# untitled.net
KiCad netlist of a schematic drawn in EAGLE
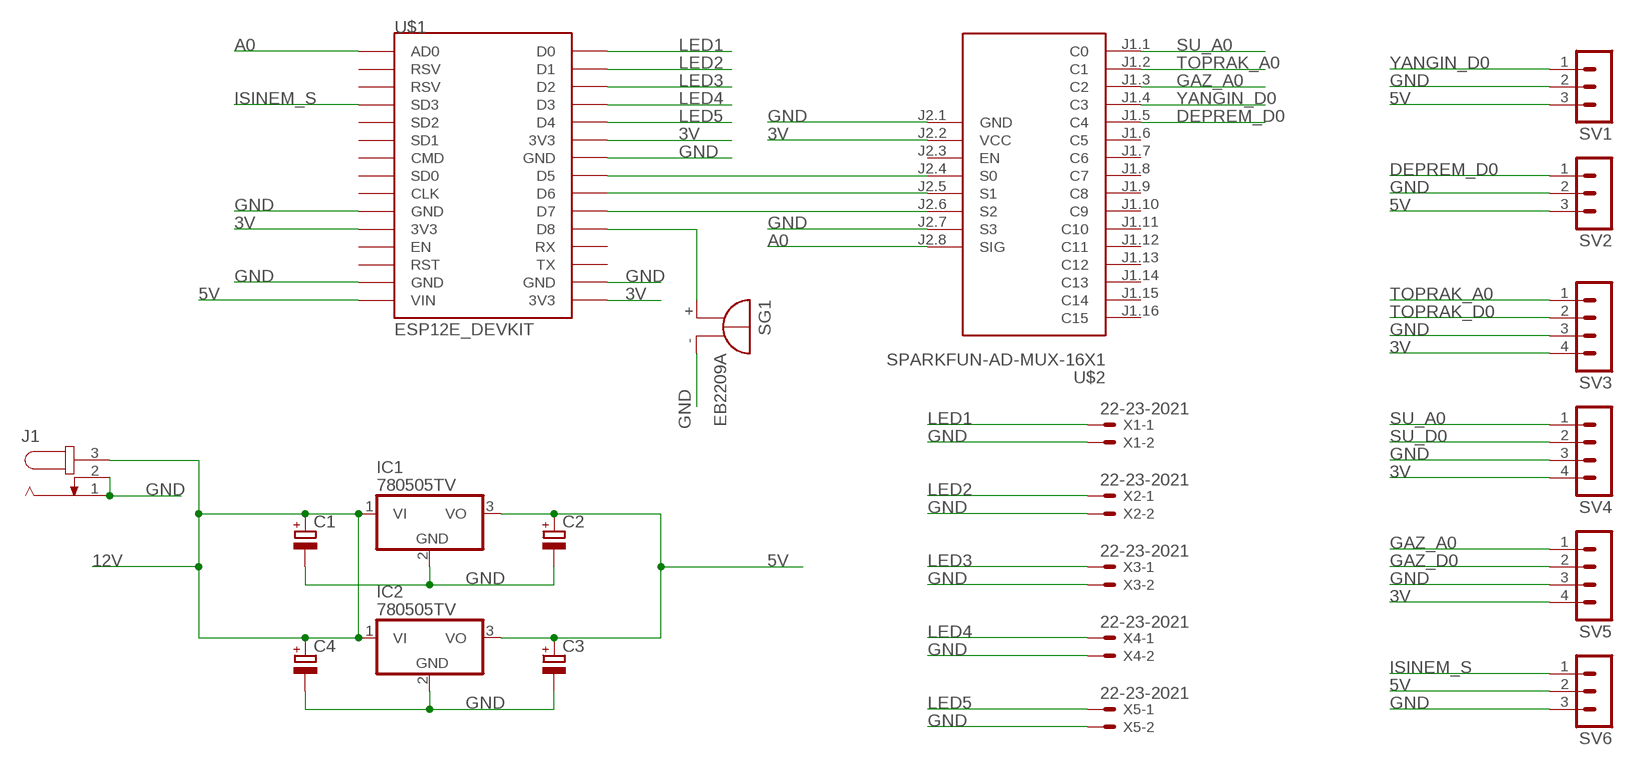
[diagram p0: schematic, sheet 1]

(export (version "E")
  (design (tool "Eeschema 10.0.6"))
  (components
    (comp (ref "C1")
      (value "CPOL-EUE5-5")
      (footprint "eagle-import:E5-5")
      (libsource (lib "eagle-import") (part "CPOL-EUE5-5"))
    )
    (comp (ref "C2")
      (value "CPOL-EUE5-5")
      (footprint "eagle-import:E5-5")
      (libsource (lib "eagle-import") (part "CPOL-EUE5-5"))
    )
    (comp (ref "C3")
      (value "CPOL-EUE5-5")
      (footprint "eagle-import:E5-5")
      (libsource (lib "eagle-import") (part "CPOL-EUE5-5"))
    )
    (comp (ref "C4")
      (value "CPOL-EUE5-5")
      (footprint "eagle-import:E5-5")
      (libsource (lib "eagle-import") (part "CPOL-EUE5-5"))
    )
    (comp (ref "IC1")
      (value "780505TV")
      (footprint "eagle-import:TO220V")
      (libsource (lib "eagle-import") (part "7805TV05"))
    )
    (comp (ref "IC2")
      (value "780505TV")
      (footprint "eagle-import:TO220V")
      (libsource (lib "eagle-import") (part "7805TV05"))
    )
    (comp (ref "J1")
      (value "JACK-PLUG1")
      (footprint "eagle-import:SPC4078")
      (libsource (lib "eagle-import") (part "JACK-PLUG1"))
    )
    (comp (ref "SG1")
      (value "EB2209A")
      (footprint "eagle-import:EB2209A")
      (libsource (lib "eagle-import") (part "EB2209A"))
    )
    (comp (ref "SV1")
      (value "MA03-1")
      (footprint "eagle-import:MA03-1")
      (libsource (lib "eagle-import") (part "MA03-1"))
    )
    (comp (ref "SV2")
      (value "MA03-1")
      (footprint "eagle-import:MA03-1")
      (libsource (lib "eagle-import") (part "MA03-1"))
    )
    (comp (ref "SV3")
      (value "MA04-1")
      (footprint "eagle-import:MA04-1")
      (libsource (lib "eagle-import") (part "MA04-1"))
    )
    (comp (ref "SV4")
      (value "MA04-1")
      (footprint "eagle-import:MA04-1")
      (libsource (lib "eagle-import") (part "MA04-1"))
    )
    (comp (ref "SV5")
      (value "MA04-1")
      (footprint "eagle-import:MA04-1")
      (libsource (lib "eagle-import") (part "MA04-1"))
    )
    (comp (ref "SV6")
      (value "MA03-1")
      (footprint "eagle-import:MA03-1")
      (libsource (lib "eagle-import") (part "MA03-1"))
    )
    (comp (ref "U$1")
      (value "ESP12E_DEVKIT")
      (footprint "eagle-import:ESP12E_DEVKIT")
      (libsource (lib "eagle-import") (part "ESP12E_DEVKIT"))
    )
    (comp (ref "U$2")
      (value "SPARKFUN-AD-MUX-16X1")
      (footprint "eagle-import:SPARKFUN-AD-MUX-16X1")
      (libsource (lib "eagle-import") (part "SPARKFUN-AD-MUX-16X1"))
    )
    (comp (ref "X1")
      (value "22-23-2021")
      (footprint "eagle-import:22-23-2021")
      (fields (field (name "MF") "MOLEX"))
      (libsource (lib "eagle-import") (part "22-23-2021"))
    )
    (comp (ref "X2")
      (value "22-23-2021")
      (footprint "eagle-import:22-23-2021")
      (fields (field (name "MF") "MOLEX"))
      (libsource (lib "eagle-import") (part "22-23-2021"))
    )
    (comp (ref "X3")
      (value "22-23-2021")
      (footprint "eagle-import:22-23-2021")
      (fields (field (name "MF") "MOLEX"))
      (libsource (lib "eagle-import") (part "22-23-2021"))
    )
    (comp (ref "X4")
      (value "22-23-2021")
      (footprint "eagle-import:22-23-2021")
      (fields (field (name "MF") "MOLEX"))
      (libsource (lib "eagle-import") (part "22-23-2021"))
    )
    (comp (ref "X5")
      (value "22-23-2021")
      (footprint "eagle-import:22-23-2021")
      (fields (field (name "MF") "MOLEX"))
      (libsource (lib "eagle-import") (part "22-23-2021"))
    )
  )
  (nets
    (net (code "1") (name "/3V") (class "Default")
      (node (ref "SV3") (pin "4") (pinfunction "4_4") (pintype "passive"))
      (node (ref "SV4") (pin "4") (pinfunction "4_4") (pintype "passive"))
      (node (ref "SV5") (pin "4") (pinfunction "4_4") (pintype "passive"))
      (node (ref "U$1") (pin "3V3@0") (pinfunction "3V3_3V3@0") (pintype "bidirectional"))
      (node (ref "U$1") (pin "3V3@1") (pinfunction "3V3_3V3@1") (pintype "bidirectional"))
      (node (ref "U$1") (pin "3V3@2") (pinfunction "3V3_3V3@2") (pintype "bidirectional"))
      (node (ref "U$2") (pin "J2.2") (pinfunction "VCC_J2.2") (pintype "power_in"))
    )
    (net (code "2") (name "/5V") (class "Default")
      (node (ref "C2") (pin "+") (pinfunction "+_+") (pintype "passive"))
      (node (ref "C3") (pin "+") (pinfunction "+_+") (pintype "passive"))
      (node (ref "IC1") (pin "3") (pinfunction "VO_3") (pintype "passive"))
      (node (ref "IC2") (pin "3") (pinfunction "VO_3") (pintype "passive"))
      (node (ref "SV1") (pin "3") (pinfunction "3_3") (pintype "passive"))
      (node (ref "SV2") (pin "3") (pinfunction "3_3") (pintype "passive"))
      (node (ref "SV6") (pin "2") (pinfunction "2_2") (pintype "passive"))
      (node (ref "U$1") (pin "VIN") (pinfunction "VIN_VIN") (pintype "bidirectional"))
    )
    (net (code "3") (name "/12V") (class "Default")
      (node (ref "C1") (pin "+") (pinfunction "+_+") (pintype "passive"))
      (node (ref "C4") (pin "+") (pinfunction "+_+") (pintype "passive"))
      (node (ref "IC1") (pin "1") (pinfunction "VI_1") (pintype "input"))
      (node (ref "IC2") (pin "1") (pinfunction "VI_1") (pintype "input"))
      (node (ref "J1") (pin "3") (pinfunction "3_3") (pintype "passive"))
    )
    (net (code "4") (name "/A0") (class "Default")
      (node (ref "U$1") (pin "AD0") (pinfunction "AD0_AD0") (pintype "bidirectional"))
      (node (ref "U$2") (pin "J2.8") (pinfunction "SIG_J2.8") (pintype "bidirectional"))
    )
    (net (code "5") (name "/DEPREM_D0") (class "Default")
      (node (ref "SV2") (pin "1") (pinfunction "1_1") (pintype "passive"))
      (node (ref "U$2") (pin "J1.5") (pinfunction "C4_J1.5") (pintype "bidirectional"))
    )
    (net (code "6") (name "/GAZ_A0") (class "Default")
      (node (ref "SV5") (pin "1") (pinfunction "1_1") (pintype "passive"))
      (node (ref "U$2") (pin "J1.3") (pinfunction "C2_J1.3") (pintype "bidirectional"))
    )
    (net (code "7") (name "/GAZ_D0") (class "Default")
      (node (ref "SV5") (pin "2") (pinfunction "2_2") (pintype "passive"))
    )
    (net (code "8") (name "/GND") (class "Default")
      (node (ref "C1") (pin "-") (pinfunction "-_-") (pintype "passive"))
      (node (ref "C2") (pin "-") (pinfunction "-_-") (pintype "passive"))
      (node (ref "C3") (pin "-") (pinfunction "-_-") (pintype "passive"))
      (node (ref "C4") (pin "-") (pinfunction "-_-") (pintype "passive"))
      (node (ref "IC1") (pin "2") (pinfunction "GND_2") (pintype "passive"))
      (node (ref "IC2") (pin "2") (pinfunction "GND_2") (pintype "passive"))
      (node (ref "J1") (pin "1") (pinfunction "1_1") (pintype "passive"))
      (node (ref "J1") (pin "2") (pinfunction "2_2") (pintype "passive"))
      (node (ref "SG1") (pin "-") (pinfunction "-_-") (pintype "passive"))
      (node (ref "SV1") (pin "2") (pinfunction "2_2") (pintype "passive"))
      (node (ref "SV2") (pin "2") (pinfunction "2_2") (pintype "passive"))
      (node (ref "SV3") (pin "3") (pinfunction "3_3") (pintype "passive"))
      (node (ref "SV4") (pin "3") (pinfunction "3_3") (pintype "passive"))
      (node (ref "SV5") (pin "3") (pinfunction "3_3") (pintype "passive"))
      (node (ref "SV6") (pin "3") (pinfunction "3_3") (pintype "passive"))
      (node (ref "U$1") (pin "GND@0") (pinfunction "GND_GND@0") (pintype "bidirectional"))
      (node (ref "U$1") (pin "GND@1") (pinfunction "GND_GND@1") (pintype "bidirectional"))
      (node (ref "U$1") (pin "GND@2") (pinfunction "GND_GND@2") (pintype "bidirectional"))
      (node (ref "U$1") (pin "GND@3") (pinfunction "GND_GND@3") (pintype "bidirectional"))
      (node (ref "U$2") (pin "J2.1") (pinfunction "GND_J2.1") (pintype "power_in"))
      (node (ref "U$2") (pin "J2.7") (pinfunction "S3_J2.7") (pintype "bidirectional"))
      (node (ref "X1") (pin "2") (pinfunction "S_2") (pintype "passive"))
      (node (ref "X2") (pin "2") (pinfunction "S_2") (pintype "passive"))
      (node (ref "X3") (pin "2") (pinfunction "S_2") (pintype "passive"))
      (node (ref "X4") (pin "2") (pinfunction "S_2") (pintype "passive"))
      (node (ref "X5") (pin "2") (pinfunction "S_2") (pintype "passive"))
    )
    (net (code "9") (name "/ISINEM_S") (class "Default")
      (node (ref "SV6") (pin "1") (pinfunction "1_1") (pintype "passive"))
      (node (ref "U$1") (pin "SD3") (pinfunction "SD3_SD3") (pintype "bidirectional"))
    )
    (net (code "10") (name "/LED1") (class "Default")
      (node (ref "U$1") (pin "D0") (pinfunction "D0_D0") (pintype "bidirectional"))
      (node (ref "X1") (pin "1") (pinfunction "S_1") (pintype "passive"))
    )
    (net (code "11") (name "/LED2") (class "Default")
      (node (ref "U$1") (pin "D1") (pinfunction "D1_D1") (pintype "bidirectional"))
      (node (ref "X2") (pin "1") (pinfunction "S_1") (pintype "passive"))
    )
    (net (code "12") (name "/LED3") (class "Default")
      (node (ref "U$1") (pin "D2") (pinfunction "D2_D2") (pintype "bidirectional"))
      (node (ref "X3") (pin "1") (pinfunction "S_1") (pintype "passive"))
    )
    (net (code "13") (name "/LED4") (class "Default")
      (node (ref "U$1") (pin "D3") (pinfunction "D3_D3") (pintype "bidirectional"))
      (node (ref "X4") (pin "1") (pinfunction "S_1") (pintype "passive"))
    )
    (net (code "14") (name "/LED5") (class "Default")
      (node (ref "U$1") (pin "D4") (pinfunction "D4_D4") (pintype "bidirectional"))
      (node (ref "X5") (pin "1") (pinfunction "S_1") (pintype "passive"))
    )
    (net (code "15") (name "/SU_A0") (class "Default")
      (node (ref "SV4") (pin "1") (pinfunction "1_1") (pintype "passive"))
      (node (ref "U$2") (pin "J1.1") (pinfunction "C0_J1.1") (pintype "bidirectional"))
    )
    (net (code "16") (name "/SU_D0") (class "Default")
      (node (ref "SV4") (pin "2") (pinfunction "2_2") (pintype "passive"))
    )
    (net (code "17") (name "/TOPRAK_A0") (class "Default")
      (node (ref "SV3") (pin "1") (pinfunction "1_1") (pintype "passive"))
      (node (ref "U$2") (pin "J1.2") (pinfunction "C1_J1.2") (pintype "bidirectional"))
    )
    (net (code "18") (name "/TOPRAK_D0") (class "Default")
      (node (ref "SV3") (pin "2") (pinfunction "2_2") (pintype "passive"))
    )
    (net (code "19") (name "/YANGIN_D0") (class "Default")
      (node (ref "SV1") (pin "1") (pinfunction "1_1") (pintype "passive"))
      (node (ref "U$2") (pin "J1.4") (pinfunction "C3_J1.4") (pintype "bidirectional"))
    )
    (net (code "20") (name "Net-(SG1-Pad+)") (class "Default")
      (node (ref "SG1") (pin "+") (pinfunction "+_+") (pintype "passive"))
      (node (ref "U$1") (pin "D8") (pinfunction "D8_D8") (pintype "bidirectional"))
    )
    (net (code "21") (name "Net-(U$2-S0)") (class "Default")
      (node (ref "U$1") (pin "D5") (pinfunction "D5_D5") (pintype "bidirectional"))
      (node (ref "U$2") (pin "J2.4") (pinfunction "S0_J2.4") (pintype "bidirectional"))
    )
    (net (code "22") (name "Net-(U$2-S1)") (class "Default")
      (node (ref "U$1") (pin "D6") (pinfunction "D6_D6") (pintype "bidirectional"))
      (node (ref "U$2") (pin "J2.5") (pinfunction "S1_J2.5") (pintype "bidirectional"))
    )
    (net (code "23") (name "Net-(U$2-S2)") (class "Default")
      (node (ref "U$1") (pin "D7") (pinfunction "D7_D7") (pintype "bidirectional"))
      (node (ref "U$2") (pin "J2.6") (pinfunction "S2_J2.6") (pintype "bidirectional"))
    )
    (net (code "24") (name "unconnected-(U$1-PadCLK)") (class "Default")
      (node (ref "U$1") (pin "CLK") (pinfunction "CLK_CLK") (pintype "bidirectional"))
    )
    (net (code "25") (name "unconnected-(U$1-PadCMD)") (class "Default")
      (node (ref "U$1") (pin "CMD") (pinfunction "CMD_CMD") (pintype "bidirectional"))
    )
    (net (code "26") (name "unconnected-(U$1-PadEN)") (class "Default")
      (node (ref "U$1") (pin "EN") (pinfunction "EN_EN") (pintype "bidirectional"))
    )
    (net (code "27") (name "unconnected-(U$1-PadRST)") (class "Default")
      (node (ref "U$1") (pin "RST") (pinfunction "RST_RST") (pintype "bidirectional"))
    )
    (net (code "28") (name "unconnected-(U$1-PadRX)") (class "Default")
      (node (ref "U$1") (pin "RX") (pinfunction "RX_RX") (pintype "bidirectional"))
    )
    (net (code "29") (name "unconnected-(U$1-PadSD0)") (class "Default")
      (node (ref "U$1") (pin "SD0") (pinfunction "SD0_SD0") (pintype "bidirectional"))
    )
    (net (code "30") (name "unconnected-(U$1-PadSD1)") (class "Default")
      (node (ref "U$1") (pin "SD1") (pinfunction "SD1_SD1") (pintype "bidirectional"))
    )
    (net (code "31") (name "unconnected-(U$1-PadSD2)") (class "Default")
      (node (ref "U$1") (pin "SD2") (pinfunction "SD2_SD2") (pintype "bidirectional"))
    )
    (net (code "32") (name "unconnected-(U$1-PadTX)") (class "Default")
      (node (ref "U$1") (pin "TX") (pinfunction "TX_TX") (pintype "bidirectional"))
    )
    (net (code "33") (name "unconnected-(U$1-RSV-PadRSV@0)") (class "Default")
      (node (ref "U$1") (pin "RSV@0") (pinfunction "RSV_RSV@0") (pintype "bidirectional"))
    )
    (net (code "34") (name "unconnected-(U$1-RSV-PadRSV@1)") (class "Default")
      (node (ref "U$1") (pin "RSV@1") (pinfunction "RSV_RSV@1") (pintype "bidirectional"))
    )
    (net (code "35") (name "unconnected-(U$2-C5-PadJ1.6)") (class "Default")
      (node (ref "U$2") (pin "J1.6") (pinfunction "C5_J1.6") (pintype "bidirectional"))
    )
    (net (code "36") (name "unconnected-(U$2-C6-PadJ1.7)") (class "Default")
      (node (ref "U$2") (pin "J1.7") (pinfunction "C6_J1.7") (pintype "bidirectional"))
    )
    (net (code "37") (name "unconnected-(U$2-C7-PadJ1.8)") (class "Default")
      (node (ref "U$2") (pin "J1.8") (pinfunction "C7_J1.8") (pintype "bidirectional"))
    )
    (net (code "38") (name "unconnected-(U$2-C8-PadJ1.9)") (class "Default")
      (node (ref "U$2") (pin "J1.9") (pinfunction "C8_J1.9") (pintype "bidirectional"))
    )
    (net (code "39") (name "unconnected-(U$2-C9-PadJ1.10)") (class "Default")
      (node (ref "U$2") (pin "J1.10") (pinfunction "C9_J1.10") (pintype "bidirectional"))
    )
    (net (code "40") (name "unconnected-(U$2-C10-PadJ1.11)") (class "Default")
      (node (ref "U$2") (pin "J1.11") (pinfunction "C10_J1.11") (pintype "bidirectional"))
    )
    (net (code "41") (name "unconnected-(U$2-C11-PadJ1.12)") (class "Default")
      (node (ref "U$2") (pin "J1.12") (pinfunction "C11_J1.12") (pintype "bidirectional"))
    )
    (net (code "42") (name "unconnected-(U$2-C12-PadJ1.13)") (class "Default")
      (node (ref "U$2") (pin "J1.13") (pinfunction "C12_J1.13") (pintype "bidirectional"))
    )
    (net (code "43") (name "unconnected-(U$2-C13-PadJ1.14)") (class "Default")
      (node (ref "U$2") (pin "J1.14") (pinfunction "C13_J1.14") (pintype "bidirectional"))
    )
    (net (code "44") (name "unconnected-(U$2-C14-PadJ1.15)") (class "Default")
      (node (ref "U$2") (pin "J1.15") (pinfunction "C14_J1.15") (pintype "bidirectional"))
    )
    (net (code "45") (name "unconnected-(U$2-C15-PadJ1.16)") (class "Default")
      (node (ref "U$2") (pin "J1.16") (pinfunction "C15_J1.16") (pintype "bidirectional"))
    )
    (net (code "46") (name "unconnected-(U$2-EN-PadJ2.3)") (class "Default")
      (node (ref "U$2") (pin "J2.3") (pinfunction "EN_J2.3") (pintype "input"))
    )
  )
)
